# RB2_My.net
KiCad netlist of a schematic drawn in Altium Designer
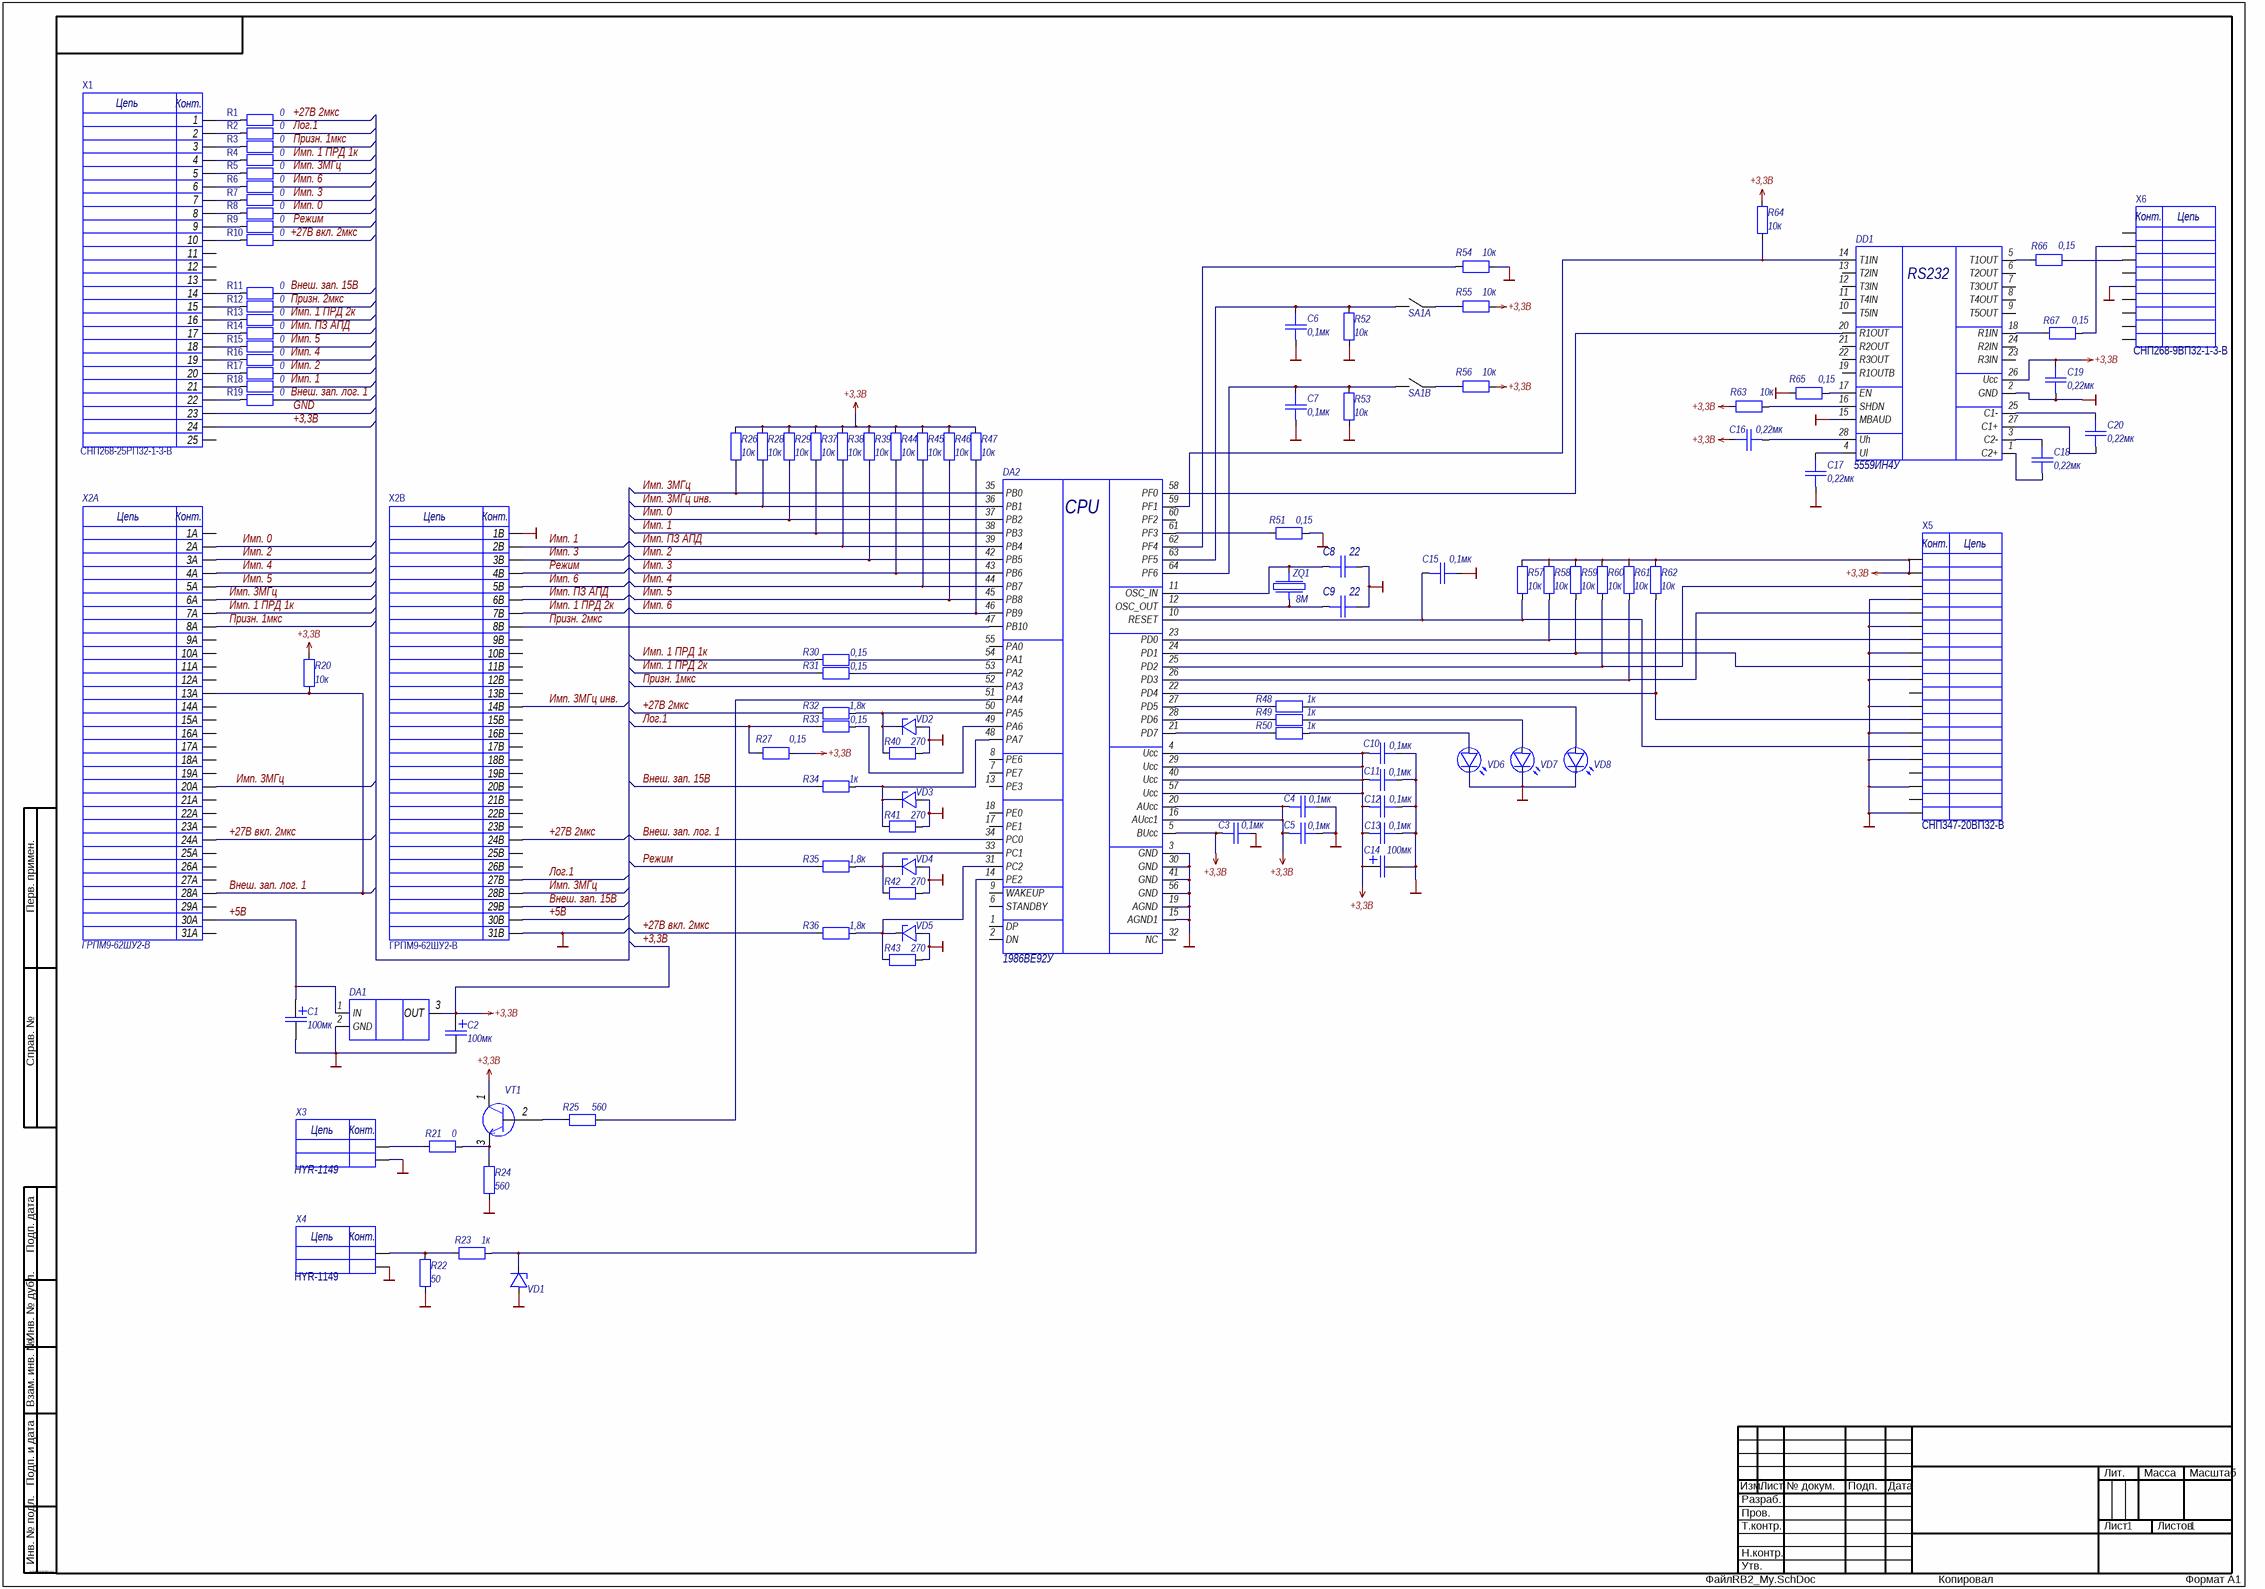
[diagram p0: RB2_My.SchDoc]

(export (version "E")
  (design (tool "Eeschema 10.0.6"))
  (components
    (comp (ref "C1")
      (value "100мк")
      (footprint "Chip2PinSM127P600-8N(E)")
      (description "Танталовый конденсатор")
      (fields (field (name "Comment") "К53-65-16В-100мкФАЖЯР.673546.004ТУ"))
      (libsource (lib "RB") (part "CapTan"))
    )
    (comp (ref "C2")
      (value "100мк")
      (footprint "Chip2PinSM127P600-8N(E)")
      (description "Танталовый конденсатор")
      (fields (field (name "Comment") "К53-65-16В-100мкФАЖЯР.673546.004ТУ"))
      (libsource (lib "RB") (part "CapTan"))
    )
    (comp (ref "C3")
      (value "0,1мк")
      (footprint "CAPC3419X15N(1206)")
      (description "Керамический конденсатор")
      (fields (field (name "Comment") "К10-17в-Н90-0,1мкФ-3ОЖО.460.107ТУ"))
      (libsource (lib "RB") (part "CapCer"))
    )
    (comp (ref "C4")
      (value "0,1мк")
      (footprint "CAPC3419X15N(1206)")
      (description "Керамический конденсатор")
      (fields (field (name "Comment") "К10-17в-Н90-0,1мкФ-3ОЖО.460.107ТУ"))
      (libsource (lib "RB") (part "CapCer"))
    )
    (comp (ref "C5")
      (value "0,1мк")
      (footprint "CAPC3419X15N(1206)")
      (description "Керамический конденсатор")
      (fields (field (name "Comment") "К10-17в-Н90-0,1мкФ-3ОЖО.460.107ТУ"))
      (libsource (lib "RB") (part "CapCer"))
    )
    (comp (ref "C6")
      (value "0,1мк")
      (footprint "CAPC3419X15N(1206)")
      (description "Керамический конденсатор")
      (fields (field (name "Comment") "К10-17в-Н90-0,1мкФ-3ОЖО.460.107ТУ"))
      (libsource (lib "RB") (part "CapCer"))
    )
    (comp (ref "C7")
      (value "0,1мк")
      (footprint "CAPC3419X15N(1206)")
      (description "Керамический конденсатор")
      (fields (field (name "Comment") "К10-17в-Н90-0,1мкФ-3ОЖО.460.107ТУ"))
      (libsource (lib "RB") (part "CapCer"))
    )
    (comp (ref "C8")
      (value "22")
      (footprint "CAPC1608X09N (0603)")
      (description "Керамический конденсатор")
      (fields (field (name "TOLERANCE") "10%") (field (name "Comment") "К10-17в-МПО-22Ф10%-1ОЖО.460.107ТУ"))
      (libsource (lib "RB") (part "CapCer_2"))
    )
    (comp (ref "C9")
      (value "22")
      (footprint "CAPC1608X09N (0603)")
      (description "Керамический конденсатор")
      (fields (field (name "TOLERANCE") "10%") (field (name "Comment") "К10-17в-МПО-22Ф10%-1ОЖО.460.107ТУ"))
      (libsource (lib "RB") (part "CapCer_2"))
    )
    (comp (ref "C10")
      (value "0,1мк")
      (footprint "CAPC3419X15N(1206)")
      (description "Керамический конденсатор")
      (fields (field (name "Comment") "К10-17в-Н90-0,1мкФ-3ОЖО.460.107ТУ"))
      (libsource (lib "RB") (part "CapCer"))
    )
    (comp (ref "C11")
      (value "0,1мк")
      (footprint "CAPC3419X15N(1206)")
      (description "Керамический конденсатор")
      (fields (field (name "Comment") "К10-17в-Н90-0,1мкФ-3ОЖО.460.107ТУ"))
      (libsource (lib "RB") (part "CapCer"))
    )
    (comp (ref "C12")
      (value "0,1мк")
      (footprint "CAPC3419X15N(1206)")
      (description "Керамический конденсатор")
      (fields (field (name "Comment") "К10-17в-Н90-0,1мкФ-3ОЖО.460.107ТУ"))
      (libsource (lib "RB") (part "CapCer"))
    )
    (comp (ref "C13")
      (value "0,1мк")
      (footprint "CAPC3419X15N(1206)")
      (description "Керамический конденсатор")
      (fields (field (name "Comment") "К10-17в-Н90-0,1мкФ-3ОЖО.460.107ТУ"))
      (libsource (lib "RB") (part "CapCer"))
    )
    (comp (ref "C14")
      (value "100мк")
      (footprint "Chip2PinSM127P600-8N(E)")
      (description "Танталовый конденсатор")
      (fields (field (name "Comment") "К53-65-16В-100мкФАЖЯР.673546.004ТУ"))
      (libsource (lib "RB") (part "CapTan"))
    )
    (comp (ref "C15")
      (value "0,1мк")
      (footprint "CAPC3419X15N(1206)")
      (description "Керамический конденсатор")
      (fields (field (name "Comment") "К10-17в-Н90-0,1мкФ-3ОЖО.460.107ТУ"))
      (libsource (lib "RB") (part "CapCer"))
    )
    (comp (ref "C16")
      (value "0,22мк")
      (footprint "CAPC3419X15N(1206)")
      (description "Керамический конденсатор")
      (fields (field (name "Comment") "К10-17в-Н30-0,22мкФ-3ОЖО.460.107ТУ"))
      (libsource (lib "RB") (part "CapCer_1"))
    )
    (comp (ref "C17")
      (value "0,22мк")
      (footprint "CAPC3419X15N(1206)")
      (description "Керамический конденсатор")
      (fields (field (name "Comment") "К10-17в-Н30-0,22мкФ-3ОЖО.460.107ТУ"))
      (libsource (lib "RB") (part "CapCer_1"))
    )
    (comp (ref "C18")
      (value "0,22мк")
      (footprint "CAPC3419X15N(1206)")
      (description "Керамический конденсатор")
      (fields (field (name "Comment") "К10-17в-Н30-0,22мкФ-3ОЖО.460.107ТУ"))
      (libsource (lib "RB") (part "CapCer_1"))
    )
    (comp (ref "C19")
      (value "0,22мк")
      (footprint "CAPC3419X15N(1206)")
      (description "Керамический конденсатор")
      (fields (field (name "Comment") "К10-17в-Н30-0,22мкФ-3ОЖО.460.107ТУ"))
      (libsource (lib "RB") (part "CapCer_1"))
    )
    (comp (ref "C20")
      (value "0,22мк")
      (footprint "CAPC3419X15N(1206)")
      (description "Керамический конденсатор")
      (fields (field (name "Comment") "К10-17в-Н30-0,22мкФ-3ОЖО.460.107ТУ"))
      (libsource (lib "RB") (part "CapCer_1"))
    )
    (comp (ref "DA1")
      (value "1303ЕН3.3ПАЕЯР.431420.638ТУ")
      (footprint "КТ-28А-2.01")
      (libsource (lib "RB") (part "Stabil"))
    )
    (comp (ref "DA2")
      (value "1986ВЕ92У")
      (footprint "1986ВЕ92У")
      (description "Микроконтроллер")
      (libsource (lib "RB") (part "1986ВЕ93"))
    )
    (comp (ref "DD1")
      (value "5559ИН4У")
      (footprint "5559ИН4У")
      (description "Приемопередатчик RS232")
      (libsource (lib "RB") (part "5559ИН4У"))
    )
    (comp (ref "R1")
      (value "0")
      (footprint "RESC1608X05N (0603)")
      (description "Резистор")
      (fields (field (name "TOLERANCE") "5%") (field (name "MANUFACTURER") "АЛЯР.434110.005ТУ"))
      (libsource (lib "RB") (part "Res_1"))
    )
    (comp (ref "R2")
      (value "0")
      (footprint "RESC1608X05N (0603)")
      (description "Резистор")
      (fields (field (name "TOLERANCE") "5%") (field (name "MANUFACTURER") "АЛЯР.434110.005ТУ"))
      (libsource (lib "RB") (part "Res_1"))
    )
    (comp (ref "R3")
      (value "0")
      (footprint "RESC1608X05N (0603)")
      (description "Резистор")
      (fields (field (name "TOLERANCE") "5%") (field (name "MANUFACTURER") "АЛЯР.434110.005ТУ"))
      (libsource (lib "RB") (part "Res_1"))
    )
    (comp (ref "R4")
      (value "0")
      (footprint "RESC1608X05N (0603)")
      (description "Резистор")
      (fields (field (name "TOLERANCE") "5%") (field (name "MANUFACTURER") "АЛЯР.434110.005ТУ"))
      (libsource (lib "RB") (part "Res_1"))
    )
    (comp (ref "R5")
      (value "0")
      (footprint "RESC1608X05N (0603)")
      (description "Резистор")
      (fields (field (name "TOLERANCE") "5%") (field (name "MANUFACTURER") "АЛЯР.434110.005ТУ"))
      (libsource (lib "RB") (part "Res_1"))
    )
    (comp (ref "R6")
      (value "0")
      (footprint "RESC1608X05N (0603)")
      (description "Резистор")
      (fields (field (name "TOLERANCE") "5%") (field (name "MANUFACTURER") "АЛЯР.434110.005ТУ"))
      (libsource (lib "RB") (part "Res_1"))
    )
    (comp (ref "R7")
      (value "0")
      (footprint "RESC1608X05N (0603)")
      (description "Резистор")
      (fields (field (name "TOLERANCE") "5%") (field (name "MANUFACTURER") "АЛЯР.434110.005ТУ"))
      (libsource (lib "RB") (part "Res_1"))
    )
    (comp (ref "R8")
      (value "0")
      (footprint "RESC1608X05N (0603)")
      (description "Резистор")
      (fields (field (name "TOLERANCE") "5%") (field (name "MANUFACTURER") "АЛЯР.434110.005ТУ"))
      (libsource (lib "RB") (part "Res_1"))
    )
    (comp (ref "R9")
      (value "0")
      (footprint "RESC1608X05N (0603)")
      (description "Резистор")
      (fields (field (name "TOLERANCE") "5%") (field (name "MANUFACTURER") "АЛЯР.434110.005ТУ"))
      (libsource (lib "RB") (part "Res_1"))
    )
    (comp (ref "R10")
      (value "0")
      (footprint "RESC1608X05N (0603)")
      (description "Резистор")
      (fields (field (name "TOLERANCE") "5%") (field (name "MANUFACTURER") "АЛЯР.434110.005ТУ"))
      (libsource (lib "RB") (part "Res_1"))
    )
    (comp (ref "R11")
      (value "0")
      (footprint "RESC1608X05N (0603)")
      (description "Резистор")
      (fields (field (name "TOLERANCE") "5%") (field (name "MANUFACTURER") "АЛЯР.434110.005ТУ"))
      (libsource (lib "RB") (part "Res_1"))
    )
    (comp (ref "R12")
      (value "0")
      (footprint "RESC1608X05N (0603)")
      (description "Резистор")
      (fields (field (name "TOLERANCE") "5%") (field (name "MANUFACTURER") "АЛЯР.434110.005ТУ"))
      (libsource (lib "RB") (part "Res_1"))
    )
    (comp (ref "R13")
      (value "0")
      (footprint "RESC1608X05N (0603)")
      (description "Резистор")
      (fields (field (name "TOLERANCE") "5%") (field (name "MANUFACTURER") "АЛЯР.434110.005ТУ"))
      (libsource (lib "RB") (part "Res_1"))
    )
    (comp (ref "R14")
      (value "0")
      (footprint "RESC1608X05N (0603)")
      (description "Резистор")
      (fields (field (name "TOLERANCE") "5%") (field (name "MANUFACTURER") "АЛЯР.434110.005ТУ"))
      (libsource (lib "RB") (part "Res_1"))
    )
    (comp (ref "R15")
      (value "0")
      (footprint "RESC1608X05N (0603)")
      (description "Резистор")
      (fields (field (name "TOLERANCE") "5%") (field (name "MANUFACTURER") "АЛЯР.434110.005ТУ"))
      (libsource (lib "RB") (part "Res_1"))
    )
    (comp (ref "R16")
      (value "0")
      (footprint "RESC1608X05N (0603)")
      (description "Резистор")
      (fields (field (name "TOLERANCE") "5%") (field (name "MANUFACTURER") "АЛЯР.434110.005ТУ"))
      (libsource (lib "RB") (part "Res_1"))
    )
    (comp (ref "R17")
      (value "0")
      (footprint "RESC1608X05N (0603)")
      (description "Резистор")
      (fields (field (name "TOLERANCE") "5%") (field (name "MANUFACTURER") "АЛЯР.434110.005ТУ"))
      (libsource (lib "RB") (part "Res_1"))
    )
    (comp (ref "R18")
      (value "0")
      (footprint "RESC1608X05N (0603)")
      (description "Резистор")
      (fields (field (name "TOLERANCE") "5%") (field (name "MANUFACTURER") "АЛЯР.434110.005ТУ"))
      (libsource (lib "RB") (part "Res_1"))
    )
    (comp (ref "R19")
      (value "0")
      (footprint "RESC1608X05N (0603)")
      (description "Резистор")
      (fields (field (name "TOLERANCE") "5%") (field (name "MANUFACTURER") "АЛЯР.434110.005ТУ"))
      (libsource (lib "RB") (part "Res_1"))
    )
    (comp (ref "R20")
      (value "10к")
      (footprint "RESC1608X05N (0603)")
      (description "Резистор")
      (fields (field (name "TOLERANCE") "5%") (field (name "MANUFACTURER") "АЛЯР.434110.005ТУ"))
      (libsource (lib "") (part "Res_7_1"))
    )
    (comp (ref "R21")
      (value "0")
      (footprint "RESC1608X05N (0603)")
      (description "Резистор")
      (fields (field (name "TOLERANCE") "5%") (field (name "MANUFACTURER") "АЛЯР.434110.005ТУ"))
      (libsource (lib "RB") (part "Res_1"))
    )
    (comp (ref "R22")
      (value "50")
      (footprint "RESC1608X05N (0603)")
      (description "Резистор")
      (fields (field (name "TOLERANCE") "5%") (field (name "MANUFACTURER") "АЛЯР.434110.005ТУ"))
      (libsource (lib "RB") (part "Res"))
    )
    (comp (ref "R23")
      (value "1к")
      (footprint "RESC1608X05N (0603)")
      (description "Резистор")
      (fields (field (name "TOLERANCE") "5%") (field (name "MANUFACTURER") "АЛЯР.434110.005ТУ"))
      (libsource (lib "RB") (part "Res_8"))
    )
    (comp (ref "R24")
      (value "560")
      (footprint "RESC1608X05N (0603)")
      (description "Резистор")
      (fields (field (name "TOLERANCE") "5%") (field (name "MANUFACTURER") "АЛЯР.434110.005ТУ"))
      (libsource (lib "RB") (part "Res_3"))
    )
    (comp (ref "R25")
      (value "560")
      (footprint "RESC1608X05N (0603)")
      (description "Резистор")
      (fields (field (name "TOLERANCE") "5%") (field (name "MANUFACTURER") "АЛЯР.434110.005ТУ"))
      (libsource (lib "") (part "Res_3_1"))
    )
    (comp (ref "R26")
      (value "10к")
      (footprint "RESC1608X05N (0603)")
      (description "Резистор")
      (fields (field (name "TOLERANCE") "5%") (field (name "MANUFACTURER") "АЛЯР.434110.005ТУ"))
      (libsource (lib "") (part "Res_7_1"))
    )
    (comp (ref "R27")
      (value "0,15")
      (footprint "RESC1608X05N (0603)")
      (description "Резистор")
      (fields (field (name "TOLERANCE") "5%") (field (name "MANUFACTURER") "АЛЯР.434110.005ТУ"))
      (libsource (lib "RB") (part "Res_4"))
    )
    (comp (ref "R28")
      (value "10к")
      (footprint "RESC1608X05N (0603)")
      (description "Резистор")
      (fields (field (name "TOLERANCE") "5%") (field (name "MANUFACTURER") "АЛЯР.434110.005ТУ"))
      (libsource (lib "") (part "Res_7_1"))
    )
    (comp (ref "R29")
      (value "10к")
      (footprint "RESC1608X05N (0603)")
      (description "Резистор")
      (fields (field (name "TOLERANCE") "5%") (field (name "MANUFACTURER") "АЛЯР.434110.005ТУ"))
      (libsource (lib "") (part "Res_7_1"))
    )
    (comp (ref "R30")
      (value "0,15")
      (footprint "RESC1608X05N (0603)")
      (description "Резистор")
      (fields (field (name "TOLERANCE") "5%") (field (name "MANUFACTURER") "АЛЯР.434110.005ТУ"))
      (libsource (lib "RB") (part "Res_4"))
    )
    (comp (ref "R31")
      (value "0,15")
      (footprint "RESC1608X05N (0603)")
      (description "Резистор")
      (fields (field (name "TOLERANCE") "5%") (field (name "MANUFACTURER") "АЛЯР.434110.005ТУ"))
      (libsource (lib "RB") (part "Res_4"))
    )
    (comp (ref "R32")
      (value "1,8к")
      (footprint "RESC1608X05N (0603)")
      (description "Резистор")
      (fields (field (name "TOLERANCE") "5%") (field (name "MANUFACTURER") "АЛЯР.434110.005ТУ"))
      (libsource (lib "RB") (part "Res_5"))
    )
    (comp (ref "R33")
      (value "0,15")
      (footprint "RESC1608X05N (0603)")
      (description "Резистор")
      (fields (field (name "TOLERANCE") "5%") (field (name "MANUFACTURER") "АЛЯР.434110.005ТУ"))
      (libsource (lib "RB") (part "Res_4"))
    )
    (comp (ref "R34")
      (value "1к")
      (footprint "RESC1608X05N (0603)")
      (description "Резистор")
      (fields (field (name "TOLERANCE") "5%") (field (name "MANUFACTURER") "АЛЯР.434110.005ТУ"))
      (libsource (lib "RB") (part "Res_8"))
    )
    (comp (ref "R35")
      (value "1,8к")
      (footprint "RESC1608X05N (0603)")
      (description "Резистор")
      (fields (field (name "TOLERANCE") "5%") (field (name "MANUFACTURER") "АЛЯР.434110.005ТУ"))
      (libsource (lib "RB") (part "Res_5"))
    )
    (comp (ref "R36")
      (value "1,8к")
      (footprint "RESC1608X05N (0603)")
      (description "Резистор")
      (fields (field (name "TOLERANCE") "5%") (field (name "MANUFACTURER") "АЛЯР.434110.005ТУ"))
      (libsource (lib "RB") (part "Res_5"))
    )
    (comp (ref "R37")
      (value "10к")
      (footprint "RESC1608X05N (0603)")
      (description "Резистор")
      (fields (field (name "TOLERANCE") "5%") (field (name "MANUFACTURER") "АЛЯР.434110.005ТУ"))
      (libsource (lib "") (part "Res_7_1"))
    )
    (comp (ref "R38")
      (value "10к")
      (footprint "RESC1608X05N (0603)")
      (description "Резистор")
      (fields (field (name "TOLERANCE") "5%") (field (name "MANUFACTURER") "АЛЯР.434110.005ТУ"))
      (libsource (lib "") (part "Res_7_1"))
    )
    (comp (ref "R39")
      (value "10к")
      (footprint "RESC1608X05N (0603)")
      (description "Резистор")
      (fields (field (name "TOLERANCE") "5%") (field (name "MANUFACTURER") "АЛЯР.434110.005ТУ"))
      (libsource (lib "") (part "Res_7_1"))
    )
    (comp (ref "R40")
      (value "270")
      (footprint "RESC1608X05N (0603)")
      (description "Резистор")
      (fields (field (name "TOLERANCE") "5%") (field (name "MANUFACTURER") "АЛЯР.434110.005ТУ"))
      (libsource (lib "RB") (part "Res_6"))
    )
    (comp (ref "R41")
      (value "270")
      (footprint "RESC1608X05N (0603)")
      (description "Резистор")
      (fields (field (name "TOLERANCE") "5%") (field (name "MANUFACTURER") "АЛЯР.434110.005ТУ"))
      (libsource (lib "RB") (part "Res_6"))
    )
    (comp (ref "R42")
      (value "270")
      (footprint "RESC1608X05N (0603)")
      (description "Резистор")
      (fields (field (name "TOLERANCE") "5%") (field (name "MANUFACTURER") "АЛЯР.434110.005ТУ"))
      (libsource (lib "RB") (part "Res_6"))
    )
    (comp (ref "R43")
      (value "270")
      (footprint "RESC1608X05N (0603)")
      (description "Резистор")
      (fields (field (name "TOLERANCE") "5%") (field (name "MANUFACTURER") "АЛЯР.434110.005ТУ"))
      (libsource (lib "RB") (part "Res_6"))
    )
    (comp (ref "R44")
      (value "10к")
      (footprint "RESC1608X05N (0603)")
      (description "Резистор")
      (fields (field (name "TOLERANCE") "5%") (field (name "MANUFACTURER") "АЛЯР.434110.005ТУ"))
      (libsource (lib "") (part "Res_7_1"))
    )
    (comp (ref "R45")
      (value "10к")
      (footprint "RESC1608X05N (0603)")
      (description "Резистор")
      (fields (field (name "TOLERANCE") "5%") (field (name "MANUFACTURER") "АЛЯР.434110.005ТУ"))
      (libsource (lib "") (part "Res_7_1"))
    )
    (comp (ref "R46")
      (value "10к")
      (footprint "RESC1608X05N (0603)")
      (description "Резистор")
      (fields (field (name "TOLERANCE") "5%") (field (name "MANUFACTURER") "АЛЯР.434110.005ТУ"))
      (libsource (lib "") (part "Res_7_1"))
    )
    (comp (ref "R47")
      (value "10к")
      (footprint "RESC1608X05N (0603)")
      (description "Резистор")
      (fields (field (name "TOLERANCE") "5%") (field (name "MANUFACTURER") "АЛЯР.434110.005ТУ"))
      (libsource (lib "") (part "Res_7_1"))
    )
    (comp (ref "R48")
      (value "1к")
      (footprint "RESC1608X05N (0603)")
      (description "Резистор")
      (fields (field (name "TOLERANCE") "5%") (field (name "MANUFACTURER") "АЛЯР.434110.005ТУ"))
      (libsource (lib "RB") (part "Res_8"))
    )
    (comp (ref "R49")
      (value "1к")
      (footprint "RESC1608X05N (0603)")
      (description "Резистор")
      (fields (field (name "TOLERANCE") "5%") (field (name "MANUFACTURER") "АЛЯР.434110.005ТУ"))
      (libsource (lib "RB") (part "Res_8"))
    )
    (comp (ref "R50")
      (value "1к")
      (footprint "RESC1608X05N (0603)")
      (description "Резистор")
      (fields (field (name "TOLERANCE") "5%") (field (name "MANUFACTURER") "АЛЯР.434110.005ТУ"))
      (libsource (lib "RB") (part "Res_8"))
    )
    (comp (ref "R51")
      (value "0,15")
      (footprint "RESC1608X05N (0603)")
      (description "Резистор")
      (fields (field (name "TOLERANCE") "5%") (field (name "MANUFACTURER") "АЛЯР.434110.005ТУ"))
      (libsource (lib "") (part "Res_4_1"))
    )
    (comp (ref "R52")
      (value "10к")
      (footprint "RESC1608X05N (0603)")
      (description "Резистор")
      (fields (field (name "TOLERANCE") "5%") (field (name "MANUFACTURER") "АЛЯР.434110.005ТУ"))
      (libsource (lib "") (part "Res_7_1"))
    )
    (comp (ref "R53")
      (value "10к")
      (footprint "RESC1608X05N (0603)")
      (description "Резистор")
      (fields (field (name "TOLERANCE") "5%") (field (name "MANUFACTURER") "АЛЯР.434110.005ТУ"))
      (libsource (lib "") (part "Res_7_1"))
    )
    (comp (ref "R54")
      (value "10к")
      (footprint "RESC1608X05N (0603)")
      (description "Резистор")
      (fields (field (name "TOLERANCE") "5%") (field (name "MANUFACTURER") "АЛЯР.434110.005ТУ"))
      (libsource (lib "") (part "Res_7_2"))
    )
    (comp (ref "R55")
      (value "10к")
      (footprint "RESC1608X05N (0603)")
      (description "Резистор")
      (fields (field (name "TOLERANCE") "5%") (field (name "MANUFACTURER") "АЛЯР.434110.005ТУ"))
      (libsource (lib "") (part "Res_7_2"))
    )
    (comp (ref "R56")
      (value "10к")
      (footprint "RESC1608X05N (0603)")
      (description "Резистор")
      (fields (field (name "TOLERANCE") "5%") (field (name "MANUFACTURER") "АЛЯР.434110.005ТУ"))
      (libsource (lib "") (part "Res_7_2"))
    )
    (comp (ref "R57")
      (value "10к")
      (footprint "RESC1608X05N (0603)")
      (description "Резистор")
      (fields (field (name "TOLERANCE") "5%") (field (name "MANUFACTURER") "АЛЯР.434110.005ТУ"))
      (libsource (lib "RB") (part "Res_7"))
    )
    (comp (ref "R58")
      (value "10к")
      (footprint "RESC1608X05N (0603)")
      (description "Резистор")
      (fields (field (name "TOLERANCE") "5%") (field (name "MANUFACTURER") "АЛЯР.434110.005ТУ"))
      (libsource (lib "RB") (part "Res_7"))
    )
    (comp (ref "R59")
      (value "10к")
      (footprint "RESC1608X05N (0603)")
      (description "Резистор")
      (fields (field (name "TOLERANCE") "5%") (field (name "MANUFACTURER") "АЛЯР.434110.005ТУ"))
      (libsource (lib "RB") (part "Res_7"))
    )
    (comp (ref "R60")
      (value "10к")
      (footprint "RESC1608X05N (0603)")
      (description "Резистор")
      (fields (field (name "TOLERANCE") "5%") (field (name "MANUFACTURER") "АЛЯР.434110.005ТУ"))
      (libsource (lib "RB") (part "Res_7"))
    )
    (comp (ref "R61")
      (value "10к")
      (footprint "RESC1608X05N (0603)")
      (description "Резистор")
      (fields (field (name "TOLERANCE") "5%") (field (name "MANUFACTURER") "АЛЯР.434110.005ТУ"))
      (libsource (lib "RB") (part "Res_7"))
    )
    (comp (ref "R62")
      (value "10к")
      (footprint "RESC1608X05N (0603)")
      (description "Резистор")
      (fields (field (name "TOLERANCE") "5%") (field (name "MANUFACTURER") "АЛЯР.434110.005ТУ"))
      (libsource (lib "RB") (part "Res_7"))
    )
    (comp (ref "R63")
      (value "10к")
      (footprint "RESC1608X05N (0603)")
      (description "Резистор")
      (fields (field (name "TOLERANCE") "5%") (field (name "MANUFACTURER") "АЛЯР.434110.005ТУ"))
      (libsource (lib "") (part "Res_7_2"))
    )
    (comp (ref "R64")
      (value "10к")
      (footprint "RESC1608X05N (0603)")
      (description "Резистор")
      (fields (field (name "TOLERANCE") "5%") (field (name "MANUFACTURER") "АЛЯР.434110.005ТУ"))
      (libsource (lib "") (part "Res_7_1"))
    )
    (comp (ref "R65")
      (value "0,15")
      (footprint "RESC1608X05N (0603)")
      (description "Резистор")
      (fields (field (name "TOLERANCE") "5%") (field (name "MANUFACTURER") "АЛЯР.434110.005ТУ"))
      (libsource (lib "RB") (part "Res_4"))
    )
    (comp (ref "R66")
      (value "0,15")
      (footprint "RESC1608X05N (0603)")
      (description "Резистор")
      (fields (field (name "TOLERANCE") "5%") (field (name "MANUFACTURER") "АЛЯР.434110.005ТУ"))
      (libsource (lib "RB") (part "Res_4"))
    )
    (comp (ref "R67")
      (value "0,15")
      (footprint "RESC1608X05N (0603)")
      (description "Резистор")
      (fields (field (name "TOLERANCE") "5%") (field (name "MANUFACTURER") "АЛЯР.434110.005ТУ"))
      (libsource (lib "RB") (part "Res_4"))
    )
    (comp (ref "SA1")
      (value "DS1040-02RN")
      (footprint "DS1040-02RN")
      (description "Переключатель")
      (libsource (lib "RB") (part "Switch"))
    )
    (comp (ref "VD1")
      (value "2С133аА0.339.092ТУ")
      (footprint "2С127Д-1")
      (libsource (lib "RB") (part "2С127Д-1"))
    )
    (comp (ref "VD2")
      (value "2С133аА0.339.092ТУ")
      (footprint "2С127Д-1")
      (libsource (lib "RB") (part "2С127Д-1"))
    )
    (comp (ref "VD3")
      (value "2С133аА0.339.092ТУ")
      (footprint "2С127Д-1")
      (libsource (lib "RB") (part "2С127Д-1"))
    )
    (comp (ref "VD4")
      (value "2С133аА0.339.092ТУ")
      (footprint "2С127Д-1")
      (libsource (lib "RB") (part "2С127Д-1"))
    )
    (comp (ref "VD5")
      (value "2С133аА0.339.092ТУ")
      (footprint "2С127Д-1")
      (libsource (lib "RB") (part "2С127Д-1"))
    )
    (comp (ref "VD6")
      (value "3Л341БаА0.339.189ТУ")
      (footprint "3Л341Б")
      (description "Индикатор")
      (libsource (lib "RB") (part "Led"))
    )
    (comp (ref "VD7")
      (value "3Л341БаА0.339.189ТУ")
      (footprint "3Л341Б")
      (description "Индикатор")
      (libsource (lib "RB") (part "Led"))
    )
    (comp (ref "VD8")
      (value "3Л341БаА0.339.189ТУ")
      (footprint "3Л341Б")
      (description "Индикатор")
      (libsource (lib "RB") (part "Led"))
    )
    (comp (ref "VT1")
      (value "2Т368А9аА0.339.092ТУ")
      (footprint "SOT100P230X95-3N (2T368A9)")
      (description "NPN транзистор")
      (libsource (lib "RB") (part "2Т368А"))
    )
    (comp (ref "X1")
      (value "СНП268-25РП32-1-3-В")
      (footprint "СНП268-25РП32-1-4-В")
      (libsource (lib "RB") (part "СНП268-25РП"))
    )
    (comp (ref "X2")
      (value "ГРПМ9-62ШУ2-В")
      (footprint "ГРПМ9-62ШУ2-В")
      (libsource (lib "RB") (part "GRPM9-62"))
    )
    (comp (ref "X3") (value "HYR-1149") (footprint "HYR-1149") (libsource (lib "RB") (part "SMA")))
    (comp (ref "X4") (value "HYR-1149") (footprint "HYR-1149") (libsource (lib "RB") (part "SMA")))
    (comp (ref "X5")
      (value "СНП347-20ВП32-В")
      (footprint "СНП347-20ВП22-В")
      (libsource (lib "RB") (part "СНП347-20ВП"))
    )
    (comp (ref "X6")
      (value "СНП268-9ВП32-1-3-В")
      (footprint "СНП268-9ВП32-1-4-В")
      (libsource (lib "RB") (part "СНП268-9ВП"))
    )
    (comp (ref "ZQ1")
      (value "8М")
      (footprint "РК456")
      (description "Кварцевый резонатор")
      (fields (field (name "Comment") "РК386-П-8ДТ-8000КТУ6321-004-07614320-96"))
      (libsource (lib "RB") (part "XTAL"))
    )
  )
  (nets
    (net (code "1") (name "+3,3В") (class "Default")
      (node (ref "C10") (pin "1") (pinfunction "1_1") (pintype "passive"))
      (node (ref "C11") (pin "1") (pinfunction "1_1") (pintype "passive"))
      (node (ref "C12") (pin "1") (pinfunction "1_1") (pintype "passive"))
      (node (ref "C13") (pin "1") (pinfunction "1_1") (pintype "passive"))
      (node (ref "C14") (pin "1") (pinfunction "1_1") (pintype "passive"))
      (node (ref "C16") (pin "2") (pinfunction "2_2") (pintype "passive"))
      (node (ref "C19") (pin "2") (pinfunction "2_2") (pintype "passive"))
      (node (ref "C2") (pin "1") (pinfunction "1_1") (pintype "passive"))
      (node (ref "C3") (pin "1") (pinfunction "1_1") (pintype "passive"))
      (node (ref "C4") (pin "1") (pinfunction "1_1") (pintype "passive"))
      (node (ref "C5") (pin "1") (pinfunction "1_1") (pintype "passive"))
      (node (ref "DA1") (pin "3") (pinfunction "OUT_3") (pintype "passive"))
      (node (ref "DA2") (pin "16") (pinfunction "AUcc1_16") (pintype "passive"))
      (node (ref "DA2") (pin "20") (pinfunction "AUcc_20") (pintype "passive"))
      (node (ref "DA2") (pin "29") (pinfunction "Ucc_29") (pintype "passive"))
      (node (ref "DA2") (pin "4") (pinfunction "Ucc_4") (pintype "passive"))
      (node (ref "DA2") (pin "40") (pinfunction "Ucc_40") (pintype "passive"))
      (node (ref "DA2") (pin "5") (pinfunction "BUcc_5") (pintype "passive"))
      (node (ref "DA2") (pin "57") (pinfunction "Ucc_57") (pintype "passive"))
      (node (ref "DD1") (pin "26") (pinfunction "Ucc_26") (pintype "passive"))
      (node (ref "R20") (pin "2") (pinfunction "2_2") (pintype "passive"))
      (node (ref "R26") (pin "2") (pinfunction "2_2") (pintype "passive"))
      (node (ref "R27") (pin "2") (pinfunction "2_2") (pintype "passive"))
      (node (ref "R28") (pin "2") (pinfunction "2_2") (pintype "passive"))
      (node (ref "R29") (pin "2") (pinfunction "2_2") (pintype "passive"))
      (node (ref "R37") (pin "2") (pinfunction "2_2") (pintype "passive"))
      (node (ref "R38") (pin "2") (pinfunction "2_2") (pintype "passive"))
      (node (ref "R39") (pin "2") (pinfunction "2_2") (pintype "passive"))
      (node (ref "R44") (pin "2") (pinfunction "2_2") (pintype "passive"))
      (node (ref "R45") (pin "2") (pinfunction "2_2") (pintype "passive"))
      (node (ref "R46") (pin "2") (pinfunction "2_2") (pintype "passive"))
      (node (ref "R47") (pin "2") (pinfunction "2_2") (pintype "passive"))
      (node (ref "R55") (pin "2") (pinfunction "2_2") (pintype "passive"))
      (node (ref "R56") (pin "2") (pinfunction "2_2") (pintype "passive"))
      (node (ref "R57") (pin "1") (pinfunction "1_1") (pintype "passive"))
      (node (ref "R58") (pin "1") (pinfunction "1_1") (pintype "passive"))
      (node (ref "R59") (pin "1") (pinfunction "1_1") (pintype "passive"))
      (node (ref "R60") (pin "1") (pinfunction "1_1") (pintype "passive"))
      (node (ref "R61") (pin "1") (pinfunction "1_1") (pintype "passive"))
      (node (ref "R62") (pin "1") (pinfunction "1_1") (pintype "passive"))
      (node (ref "R63") (pin "1") (pinfunction "1_1") (pintype "passive"))
      (node (ref "R64") (pin "2") (pinfunction "2_2") (pintype "passive"))
      (node (ref "VT1") (pin "1") (pinfunction "1_1") (pintype "passive"))
      (node (ref "X1") (pin "24") (pinfunction "24_24") (pintype "passive"))
      (node (ref "X5") (pin "1") (pintype "passive"))
      (node (ref "X5") (pin "2") (pintype "passive"))
    )
    (net (code "2") (name "/+5В") (class "Default")
      (node (ref "C1") (pin "1") (pinfunction "1_1") (pintype "passive"))
      (node (ref "DA1") (pin "1") (pinfunction "IN_1") (pintype "passive"))
      (node (ref "X2") (pin "30A") (pinfunction "30A_30A") (pintype "passive"))
      (node (ref "X2") (pin "30B") (pinfunction "30B_30B") (pintype "passive"))
    )
    (net (code "3") (name "/+27В 2мкс") (class "Default")
      (node (ref "R1") (pin "2") (pinfunction "2_2") (pintype "passive"))
      (node (ref "R32") (pin "1") (pinfunction "1_1") (pintype "passive"))
      (node (ref "X2") (pin "24B") (pinfunction "24B_24B") (pintype "passive"))
    )
    (net (code "4") (name "/+27В вкл. 2мкс") (class "Default")
      (node (ref "R10") (pin "2") (pinfunction "2_2") (pintype "passive"))
      (node (ref "R36") (pin "1") (pinfunction "1_1") (pintype "passive"))
      (node (ref "X2") (pin "24A") (pinfunction "24A_24A") (pintype "passive"))
    )
    (net (code "5") (name "/Внеш. зап. 15В") (class "Default")
      (node (ref "R11") (pin "2") (pinfunction "2_2") (pintype "passive"))
      (node (ref "R34") (pin "1") (pinfunction "1_1") (pintype "passive"))
      (node (ref "X2") (pin "29B") (pinfunction "29B_29B") (pintype "passive"))
    )
    (net (code "6") (name "/Внеш. зап. лог. 1") (class "Default")
      (node (ref "DA2") (pin "34") (pinfunction "PC0_34") (pintype "passive"))
      (node (ref "R19") (pin "2") (pinfunction "2_2") (pintype "passive"))
      (node (ref "R20") (pin "1") (pinfunction "1_1") (pintype "passive"))
      (node (ref "X2") (pin "13A") (pinfunction "13A_13A") (pintype "passive"))
      (node (ref "X2") (pin "28A") (pinfunction "28A_28A") (pintype "passive"))
    )
    (net (code "7") (name "/Имп. 0") (class "Default")
      (node (ref "DA2") (pin "37") (pinfunction "PB2_37") (pintype "passive"))
      (node (ref "R29") (pin "1") (pinfunction "1_1") (pintype "passive"))
      (node (ref "R8") (pin "2") (pinfunction "2_2") (pintype "passive"))
      (node (ref "X2") (pin "2A") (pinfunction "2A_2A") (pintype "passive"))
    )
    (net (code "8") (name "/Имп. 1") (class "Default")
      (node (ref "DA2") (pin "38") (pinfunction "PB3_38") (pintype "passive"))
      (node (ref "R18") (pin "2") (pinfunction "2_2") (pintype "passive"))
      (node (ref "R37") (pin "1") (pinfunction "1_1") (pintype "passive"))
      (node (ref "X2") (pin "2B") (pinfunction "2B_2B") (pintype "passive"))
    )
    (net (code "9") (name "/Имп. 1 ПРД 1к") (class "Default")
      (node (ref "R30") (pin "1") (pinfunction "1_1") (pintype "passive"))
      (node (ref "R4") (pin "2") (pinfunction "2_2") (pintype "passive"))
      (node (ref "X2") (pin "7A") (pinfunction "7A_7A") (pintype "passive"))
    )
    (net (code "10") (name "/Имп. 1 ПРД 2к") (class "Default")
      (node (ref "R13") (pin "2") (pinfunction "2_2") (pintype "passive"))
      (node (ref "R31") (pin "1") (pinfunction "1_1") (pintype "passive"))
      (node (ref "X2") (pin "7B") (pinfunction "7B_7B") (pintype "passive"))
    )
    (net (code "11") (name "/Имп. 2") (class "Default")
      (node (ref "DA2") (pin "42") (pinfunction "PB5_42") (pintype "passive"))
      (node (ref "R17") (pin "2") (pinfunction "2_2") (pintype "passive"))
      (node (ref "R39") (pin "1") (pinfunction "1_1") (pintype "passive"))
      (node (ref "X2") (pin "3A") (pinfunction "3A_3A") (pintype "passive"))
    )
    (net (code "12") (name "/Имп. 3") (class "Default")
      (node (ref "DA2") (pin "43") (pinfunction "PB6_43") (pintype "passive"))
      (node (ref "R44") (pin "1") (pinfunction "1_1") (pintype "passive"))
      (node (ref "R7") (pin "2") (pinfunction "2_2") (pintype "passive"))
      (node (ref "X2") (pin "3B") (pinfunction "3B_3B") (pintype "passive"))
    )
    (net (code "13") (name "/Имп. 3МГц") (class "Default")
      (node (ref "DA2") (pin "35") (pinfunction "PB0_35") (pintype "passive"))
      (node (ref "R26") (pin "1") (pinfunction "1_1") (pintype "passive"))
      (node (ref "R5") (pin "2") (pinfunction "2_2") (pintype "passive"))
      (node (ref "X2") (pin "20A") (pinfunction "20A_20A") (pintype "passive"))
      (node (ref "X2") (pin "28B") (pinfunction "28B_28B") (pintype "passive"))
      (node (ref "X2") (pin "6A") (pinfunction "6A_6A") (pintype "passive"))
    )
    (net (code "14") (name "/Имп. 3МГц инв.") (class "Default")
      (node (ref "DA2") (pin "36") (pinfunction "PB1_36") (pintype "passive"))
      (node (ref "R28") (pin "1") (pinfunction "1_1") (pintype "passive"))
      (node (ref "X2") (pin "14B") (pinfunction "14B_14B") (pintype "passive"))
    )
    (net (code "15") (name "/Имп. 4") (class "Default")
      (node (ref "DA2") (pin "44") (pinfunction "PB7_44") (pintype "passive"))
      (node (ref "R16") (pin "2") (pinfunction "2_2") (pintype "passive"))
      (node (ref "R45") (pin "1") (pinfunction "1_1") (pintype "passive"))
      (node (ref "X2") (pin "4A") (pinfunction "4A_4A") (pintype "passive"))
    )
    (net (code "16") (name "/Имп. 5") (class "Default")
      (node (ref "DA2") (pin "45") (pinfunction "PB8_45") (pintype "passive"))
      (node (ref "R15") (pin "2") (pinfunction "2_2") (pintype "passive"))
      (node (ref "R46") (pin "1") (pinfunction "1_1") (pintype "passive"))
      (node (ref "X2") (pin "5A") (pinfunction "5A_5A") (pintype "passive"))
    )
    (net (code "17") (name "/Имп. 6") (class "Default")
      (node (ref "DA2") (pin "46") (pinfunction "PB9_46") (pintype "passive"))
      (node (ref "R47") (pin "1") (pinfunction "1_1") (pintype "passive"))
      (node (ref "R6") (pin "2") (pinfunction "2_2") (pintype "passive"))
      (node (ref "X2") (pin "5B") (pinfunction "5B_5B") (pintype "passive"))
    )
    (net (code "18") (name "/Имп. ПЗ АПД") (class "Default")
      (node (ref "DA2") (pin "39") (pinfunction "PB4_39") (pintype "passive"))
      (node (ref "R14") (pin "2") (pinfunction "2_2") (pintype "passive"))
      (node (ref "R38") (pin "1") (pinfunction "1_1") (pintype "passive"))
      (node (ref "X2") (pin "6B") (pinfunction "6B_6B") (pintype "passive"))
    )
    (net (code "19") (name "/Лог.1") (class "Default")
      (node (ref "R2") (pin "2") (pinfunction "2_2") (pintype "passive"))
      (node (ref "R27") (pin "1") (pinfunction "1_1") (pintype "passive"))
      (node (ref "R33") (pin "1") (pinfunction "1_1") (pintype "passive"))
      (node (ref "X2") (pin "27B") (pinfunction "27B_27B") (pintype "passive"))
    )
    (net (code "20") (name "/Призн. 1мкс") (class "Default")
      (node (ref "DA2") (pin "52") (pinfunction "PA3_52") (pintype "passive"))
      (node (ref "R3") (pin "2") (pinfunction "2_2") (pintype "passive"))
      (node (ref "X2") (pin "8A") (pinfunction "8A_8A") (pintype "passive"))
    )
    (net (code "21") (name "/Призн. 2мкс") (class "Default")
      (node (ref "DA2") (pin "47") (pinfunction "PB10_47") (pintype "passive"))
      (node (ref "R12") (pin "2") (pinfunction "2_2") (pintype "passive"))
      (node (ref "X2") (pin "8B") (pinfunction "8B_8B") (pintype "passive"))
    )
    (net (code "22") (name "/Режим") (class "Default")
      (node (ref "R35") (pin "1") (pinfunction "1_1") (pintype "passive"))
      (node (ref "R9") (pin "2") (pinfunction "2_2") (pintype "passive"))
      (node (ref "X2") (pin "4B") (pinfunction "4B_4B") (pintype "passive"))
    )
    (net (code "23") (name "GND") (class "Default")
      (node (ref "C1") (pin "2") (pinfunction "2_2") (pintype "passive"))
      (node (ref "C10") (pin "2") (pinfunction "2_2") (pintype "passive"))
      (node (ref "C11") (pin "2") (pinfunction "2_2") (pintype "passive"))
      (node (ref "C12") (pin "2") (pinfunction "2_2") (pintype "passive"))
      (node (ref "C13") (pin "2") (pinfunction "2_2") (pintype "passive"))
      (node (ref "C14") (pin "2") (pinfunction "2_2") (pintype "passive"))
      (node (ref "C15") (pin "2") (pinfunction "2_2") (pintype "passive"))
      (node (ref "C17") (pin "1") (pinfunction "1_1") (pintype "passive"))
      (node (ref "C19") (pin "1") (pinfunction "1_1") (pintype "passive"))
      (node (ref "C2") (pin "2") (pinfunction "2_2") (pintype "passive"))
      (node (ref "C3") (pin "2") (pinfunction "2_2") (pintype "passive"))
      (node (ref "C4") (pin "2") (pinfunction "2_2") (pintype "passive"))
      (node (ref "C5") (pin "2") (pinfunction "2_2") (pintype "passive"))
      (node (ref "C6") (pin "1") (pinfunction "1_1") (pintype "passive"))
      (node (ref "C7") (pin "1") (pinfunction "1_1") (pintype "passive"))
      (node (ref "C8") (pin "2") (pinfunction "2_2") (pintype "passive"))
      (node (ref "C9") (pin "2") (pinfunction "2_2") (pintype "passive"))
      (node (ref "DA1") (pin "2") (pinfunction "GND_2") (pintype "passive"))
      (node (ref "DA2") (pin "15") (pinfunction "AGND1_15") (pintype "passive"))
      (node (ref "DA2") (pin "19") (pinfunction "AGND_19") (pintype "passive"))
      (node (ref "DA2") (pin "3") (pinfunction "GND_3") (pintype "passive"))
      (node (ref "DA2") (pin "30") (pinfunction "GND_30") (pintype "passive"))
      (node (ref "DA2") (pin "41") (pinfunction "GND_41") (pintype "passive"))
      (node (ref "DA2") (pin "56") (pinfunction "GND_56") (pintype "passive"))
      (node (ref "DD1") (pin "15") (pinfunction "MBAUD_15") (pintype "passive"))
      (node (ref "DD1") (pin "2") (pinfunction "GND_2") (pintype "passive"))
      (node (ref "R22") (pin "1") (pinfunction "1_1") (pintype "passive"))
      (node (ref "R24") (pin "1") (pinfunction "1_1") (pintype "passive"))
      (node (ref "R40") (pin "2") (pinfunction "2_2") (pintype "passive"))
      (node (ref "R41") (pin "2") (pinfunction "2_2") (pintype "passive"))
      (node (ref "R42") (pin "2") (pinfunction "2_2") (pintype "passive"))
      (node (ref "R43") (pin "2") (pinfunction "2_2") (pintype "passive"))
      (node (ref "R51") (pin "1") (pinfunction "1_1") (pintype "passive"))
      (node (ref "R52") (pin "1") (pinfunction "1_1") (pintype "passive"))
      (node (ref "R53") (pin "1") (pinfunction "1_1") (pintype "passive"))
      (node (ref "R54") (pin "2") (pinfunction "2_2") (pintype "passive"))
      (node (ref "R65") (pin "1") (pinfunction "1_1") (pintype "passive"))
      (node (ref "VD1") (pin "1") (pinfunction "1_1") (pintype "passive"))
      (node (ref "VD2") (pin "1") (pinfunction "1_1") (pintype "passive"))
      (node (ref "VD3") (pin "1") (pinfunction "1_1") (pintype "passive"))
      (node (ref "VD4") (pin "1") (pinfunction "1_1") (pintype "passive"))
      (node (ref "VD5") (pin "1") (pinfunction "1_1") (pintype "passive"))
      (node (ref "VD6") (pin "2") (pinfunction "2_2") (pintype "passive"))
      (node (ref "VD7") (pin "2") (pinfunction "2_2") (pintype "passive"))
      (node (ref "VD8") (pin "2") (pinfunction "2_2") (pintype "passive"))
      (node (ref "X1") (pin "23") (pinfunction "23_23") (pintype "passive"))
      (node (ref "X2") (pin "1B") (pinfunction "1B_1B") (pintype "passive"))
      (node (ref "X2") (pin "31B") (pinfunction "31B_31B") (pintype "passive"))
      (node (ref "X3") (pin "2") (pintype "passive"))
      (node (ref "X4") (pin "2") (pintype "passive"))
      (node (ref "X5") (pin "10") (pintype "passive"))
      (node (ref "X5") (pin "12") (pintype "passive"))
      (node (ref "X5") (pin "14") (pintype "passive"))
      (node (ref "X5") (pin "16") (pintype "passive"))
      (node (ref "X5") (pin "18") (pintype "passive"))
      (node (ref "X5") (pin "20") (pintype "passive"))
      (node (ref "X5") (pin "4") (pintype "passive"))
      (node (ref "X5") (pin "6") (pintype "passive"))
      (node (ref "X5") (pin "8") (pintype "passive"))
      (node (ref "X6") (pin "5") (pintype "power_in"))
    )
    (net (code "24") (name "Net-(DA2-OSC_IN)") (class "Default")
      (node (ref "C8") (pin "1") (pinfunction "1_1") (pintype "passive"))
      (node (ref "DA2") (pin "11") (pinfunction "OSC_IN_11") (pintype "passive"))
      (node (ref "ZQ1") (pin "2") (pinfunction "OSC2_2") (pintype "passive"))
    )
    (net (code "25") (name "Net-(DA2-OSC_OUT)") (class "Default")
      (node (ref "C9") (pin "1") (pinfunction "1_1") (pintype "passive"))
      (node (ref "DA2") (pin "12") (pinfunction "OSC_OUT_12") (pintype "passive"))
      (node (ref "ZQ1") (pin "1") (pinfunction "OSC1_1") (pintype "passive"))
    )
    (net (code "26") (name "Net-(DA2-PA1)") (class "Default")
      (node (ref "DA2") (pin "54") (pinfunction "PA1_54") (pintype "passive"))
      (node (ref "R30") (pin "2") (pinfunction "2_2") (pintype "passive"))
    )
    (net (code "27") (name "Net-(DA2-PA2)") (class "Default")
      (node (ref "DA2") (pin "53") (pinfunction "PA2_53") (pintype "passive"))
      (node (ref "R31") (pin "2") (pinfunction "2_2") (pintype "passive"))
    )
    (net (code "28") (name "Net-(DA2-PA4)") (class "Default")
      (node (ref "DA2") (pin "51") (pinfunction "PA4_51") (pintype "passive"))
      (node (ref "R25") (pin "1") (pinfunction "1_1") (pintype "passive"))
    )
    (net (code "29") (name "Net-(DA2-PA5)") (class "Default")
      (node (ref "DA2") (pin "50") (pinfunction "PA5_50") (pintype "passive"))
      (node (ref "R32") (pin "2") (pinfunction "2_2") (pintype "passive"))
      (node (ref "R40") (pin "1") (pinfunction "1_1") (pintype "passive"))
      (node (ref "VD2") (pin "2") (pinfunction "2_2") (pintype "passive"))
    )
    (net (code "30") (name "Net-(DA2-PA6)") (class "Default")
      (node (ref "DA2") (pin "49") (pinfunction "PA6_49") (pintype "passive"))
      (node (ref "R33") (pin "2") (pinfunction "2_2") (pintype "passive"))
    )
    (net (code "31") (name "Net-(DA2-PA7)") (class "Default")
      (node (ref "DA2") (pin "48") (pinfunction "PA7_48") (pintype "passive"))
      (node (ref "R34") (pin "2") (pinfunction "2_2") (pintype "passive"))
      (node (ref "R41") (pin "1") (pinfunction "1_1") (pintype "passive"))
      (node (ref "VD3") (pin "2") (pinfunction "2_2") (pintype "passive"))
    )
    (net (code "32") (name "Net-(DA2-PC1)") (class "Default")
      (node (ref "DA2") (pin "33") (pinfunction "PC1_33") (pintype "passive"))
      (node (ref "R35") (pin "2") (pinfunction "2_2") (pintype "passive"))
      (node (ref "R42") (pin "1") (pinfunction "1_1") (pintype "passive"))
      (node (ref "VD4") (pin "2") (pinfunction "2_2") (pintype "passive"))
    )
    (net (code "33") (name "Net-(DA2-PC2)") (class "Default")
      (node (ref "DA2") (pin "31") (pinfunction "PC2_31") (pintype "passive"))
      (node (ref "R36") (pin "2") (pinfunction "2_2") (pintype "passive"))
      (node (ref "R43") (pin "1") (pinfunction "1_1") (pintype "passive"))
      (node (ref "VD5") (pin "2") (pinfunction "2_2") (pintype "passive"))
    )
    (net (code "34") (name "Net-(DA2-PD0)") (class "Default")
      (node (ref "DA2") (pin "23") (pinfunction "PD0_23") (pintype "passive"))
      (node (ref "R58") (pin "2") (pinfunction "2_2") (pintype "passive"))
      (node (ref "X5") (pin "7") (pintype "passive"))
    )
    (net (code "35") (name "Net-(DA2-PD1)") (class "Default")
      (node (ref "DA2") (pin "24") (pinfunction "PD1_24") (pintype "passive"))
      (node (ref "R59") (pin "2") (pinfunction "2_2") (pintype "passive"))
      (node (ref "X5") (pin "9") (pintype "passive"))
    )
    (net (code "36") (name "Net-(DA2-PD2)") (class "Default")
      (node (ref "DA2") (pin "25") (pinfunction "PD2_25") (pintype "passive"))
      (node (ref "R60") (pin "2") (pinfunction "2_2") (pintype "passive"))
      (node (ref "X5") (pin "3") (pintype "passive"))
    )
    (net (code "37") (name "Net-(DA2-PD3)") (class "Default")
      (node (ref "DA2") (pin "26") (pinfunction "PD3_26") (pintype "passive"))
      (node (ref "R61") (pin "2") (pinfunction "2_2") (pintype "passive"))
      (node (ref "X5") (pin "5") (pintype "passive"))
    )
    (net (code "38") (name "Net-(DA2-PD4)") (class "Default")
      (node (ref "DA2") (pin "22") (pinfunction "PD4_22") (pintype "passive"))
      (node (ref "R62") (pin "2") (pinfunction "2_2") (pintype "passive"))
      (node (ref "X5") (pin "13") (pintype "passive"))
    )
    (net (code "39") (name "Net-(DA2-PD5)") (class "Default")
      (node (ref "DA2") (pin "27") (pinfunction "PD5_27") (pintype "passive"))
      (node (ref "R48") (pin "1") (pinfunction "1_1") (pintype "passive"))
    )
    (net (code "40") (name "Net-(DA2-PD6)") (class "Default")
      (node (ref "DA2") (pin "28") (pinfunction "PD6_28") (pintype "passive"))
      (node (ref "R49") (pin "1") (pinfunction "1_1") (pintype "passive"))
    )
    (net (code "41") (name "Net-(DA2-PD7)") (class "Default")
      (node (ref "DA2") (pin "21") (pinfunction "PD7_21") (pintype "passive"))
      (node (ref "R50") (pin "1") (pinfunction "1_1") (pintype "passive"))
    )
    (net (code "42") (name "Net-(DA2-PE2)") (class "Default")
      (node (ref "DA2") (pin "14") (pinfunction "PE2_14") (pintype "passive"))
      (node (ref "R23") (pin "2") (pinfunction "2_2") (pintype "passive"))
      (node (ref "VD1") (pin "2") (pinfunction "2_2") (pintype "passive"))
    )
    (net (code "43") (name "Net-(DA2-PF0)") (class "Default")
      (node (ref "DA2") (pin "58") (pinfunction "PF0_58") (pintype "passive"))
      (node (ref "DD1") (pin "20") (pinfunction "R1OUT_20") (pintype "passive"))
    )
    (net (code "44") (name "Net-(DA2-PF1)") (class "Default")
      (node (ref "DA2") (pin "59") (pinfunction "PF1_59") (pintype "passive"))
      (node (ref "DD1") (pin "14") (pinfunction "T1IN_14") (pintype "passive"))
      (node (ref "R64") (pin "1") (pinfunction "1_1") (pintype "passive"))
    )
    (net (code "45") (name "Net-(DA2-PF3)") (class "Default")
      (node (ref "DA2") (pin "61") (pinfunction "PF3_61") (pintype "passive"))
      (node (ref "R51") (pin "2") (pinfunction "2_2") (pintype "passive"))
    )
    (net (code "46") (name "Net-(DA2-PF4)") (class "Default")
      (node (ref "DA2") (pin "62") (pinfunction "PF4_62") (pintype "passive"))
      (node (ref "R54") (pin "1") (pinfunction "1_1") (pintype "passive"))
    )
    (net (code "47") (name "Net-(DA2-PF5)") (class "Default")
      (node (ref "C6") (pin "2") (pinfunction "2_2") (pintype "passive"))
      (node (ref "DA2") (pin "63") (pinfunction "PF5_63") (pintype "passive"))
      (node (ref "R52") (pin "2") (pinfunction "2_2") (pintype "passive"))
      (node (ref "SA1") (pin "2") (pinfunction "2_2") (pintype "passive"))
    )
    (net (code "48") (name "Net-(DA2-PF6)") (class "Default")
      (node (ref "C7") (pin "2") (pinfunction "2_2") (pintype "passive"))
      (node (ref "DA2") (pin "64") (pinfunction "PF6_64") (pintype "passive"))
      (node (ref "R53") (pin "2") (pinfunction "2_2") (pintype "passive"))
      (node (ref "SA1") (pin "4") (pinfunction "4_4") (pintype "passive"))
    )
    (net (code "49") (name "Net-(DA2-RESET)") (class "Default")
      (node (ref "C15") (pin "1") (pinfunction "1_1") (pintype "passive"))
      (node (ref "DA2") (pin "10") (pinfunction "RESET_10") (pintype "passive"))
      (node (ref "R57") (pin "2") (pinfunction "2_2") (pintype "passive"))
      (node (ref "X5") (pin "15") (pintype "passive"))
    )
    (net (code "50") (name "Net-(DD1-C1+)") (class "Default")
      (node (ref "C20") (pin "1") (pinfunction "1_1") (pintype "passive"))
      (node (ref "DD1") (pin "27") (pinfunction "C1+_27") (pintype "passive"))
    )
    (net (code "51") (name "Net-(DD1-C1-)") (class "Default")
      (node (ref "C20") (pin "2") (pinfunction "2_2") (pintype "passive"))
      (node (ref "DD1") (pin "25") (pinfunction "C1-_25") (pintype "passive"))
    )
    (net (code "52") (name "Net-(DD1-C2+)") (class "Default")
      (node (ref "C18") (pin "1") (pinfunction "1_1") (pintype "passive"))
      (node (ref "DD1") (pin "1") (pinfunction "C2+_1") (pintype "passive"))
    )
    (net (code "53") (name "Net-(DD1-C2-)") (class "Default")
      (node (ref "C18") (pin "2") (pinfunction "2_2") (pintype "passive"))
      (node (ref "DD1") (pin "3") (pinfunction "C2-_3") (pintype "passive"))
    )
    (net (code "54") (name "Net-(DD1-EN)") (class "Default")
      (node (ref "DD1") (pin "17") (pinfunction "EN_17") (pintype "passive"))
      (node (ref "R65") (pin "2") (pinfunction "2_2") (pintype "passive"))
    )
    (net (code "55") (name "Net-(DD1-R1IN)") (class "Default")
      (node (ref "DD1") (pin "18") (pinfunction "R1IN_18") (pintype "passive"))
      (node (ref "R67") (pin "1") (pinfunction "1_1") (pintype "passive"))
    )
    (net (code "56") (name "Net-(DD1-SHDN)") (class "Default")
      (node (ref "DD1") (pin "16") (pinfunction "SHDN_16") (pintype "passive"))
      (node (ref "R63") (pin "2") (pinfunction "2_2") (pintype "passive"))
    )
    (net (code "57") (name "Net-(DD1-T1OUT)") (class "Default")
      (node (ref "DD1") (pin "5") (pinfunction "T1OUT_5") (pintype "passive"))
      (node (ref "R66") (pin "1") (pinfunction "1_1") (pintype "passive"))
    )
    (net (code "58") (name "Net-(DD1-Uh)") (class "Default")
      (node (ref "C16") (pin "1") (pinfunction "1_1") (pintype "passive"))
      (node (ref "DD1") (pin "28") (pinfunction "Uh_28") (pintype "passive"))
    )
    (net (code "59") (name "Net-(DD1-Ul)") (class "Default")
      (node (ref "C17") (pin "2") (pinfunction "2_2") (pintype "passive"))
      (node (ref "DD1") (pin "4") (pinfunction "Ul_4") (pintype "passive"))
    )
    (net (code "60") (name "Net-(R1-Pad1)") (class "Default")
      (node (ref "R1") (pin "1") (pinfunction "1_1") (pintype "passive"))
      (node (ref "X1") (pin "1") (pinfunction "1_1") (pintype "passive"))
    )
    (net (code "61") (name "Net-(R2-Pad1)") (class "Default")
      (node (ref "R2") (pin "1") (pinfunction "1_1") (pintype "passive"))
      (node (ref "X1") (pin "2") (pinfunction "2_2") (pintype "passive"))
    )
    (net (code "62") (name "Net-(R3-Pad1)") (class "Default")
      (node (ref "R3") (pin "1") (pinfunction "1_1") (pintype "passive"))
      (node (ref "X1") (pin "3") (pinfunction "3_3") (pintype "passive"))
    )
    (net (code "63") (name "Net-(R4-Pad1)") (class "Default")
      (node (ref "R4") (pin "1") (pinfunction "1_1") (pintype "passive"))
      (node (ref "X1") (pin "4") (pinfunction "4_4") (pintype "passive"))
    )
    (net (code "64") (name "Net-(R5-Pad1)") (class "Default")
      (node (ref "R5") (pin "1") (pinfunction "1_1") (pintype "passive"))
      (node (ref "X1") (pin "5") (pinfunction "5_5") (pintype "passive"))
    )
    (net (code "65") (name "Net-(R6-Pad1)") (class "Default")
      (node (ref "R6") (pin "1") (pinfunction "1_1") (pintype "passive"))
      (node (ref "X1") (pin "6") (pinfunction "6_6") (pintype "passive"))
    )
    (net (code "66") (name "Net-(R7-Pad1)") (class "Default")
      (node (ref "R7") (pin "1") (pinfunction "1_1") (pintype "passive"))
      (node (ref "X1") (pin "7") (pinfunction "7_7") (pintype "passive"))
    )
    (net (code "67") (name "Net-(R8-Pad1)") (class "Default")
      (node (ref "R8") (pin "1") (pinfunction "1_1") (pintype "passive"))
      (node (ref "X1") (pin "8") (pinfunction "8_8") (pintype "passive"))
    )
    (net (code "68") (name "Net-(R9-Pad1)") (class "Default")
      (node (ref "R9") (pin "1") (pinfunction "1_1") (pintype "passive"))
      (node (ref "X1") (pin "9") (pinfunction "9_9") (pintype "passive"))
    )
    (net (code "69") (name "Net-(R10-Pad1)") (class "Default")
      (node (ref "R10") (pin "1") (pinfunction "1_1") (pintype "passive"))
      (node (ref "X1") (pin "10") (pinfunction "10_10") (pintype "passive"))
    )
    (net (code "70") (name "Net-(R11-Pad1)") (class "Default")
      (node (ref "R11") (pin "1") (pinfunction "1_1") (pintype "passive"))
      (node (ref "X1") (pin "14") (pinfunction "14_14") (pintype "passive"))
    )
    (net (code "71") (name "Net-(R12-Pad1)") (class "Default")
      (node (ref "R12") (pin "1") (pinfunction "1_1") (pintype "passive"))
      (node (ref "X1") (pin "15") (pinfunction "15_15") (pintype "passive"))
    )
    (net (code "72") (name "Net-(R13-Pad1)") (class "Default")
      (node (ref "R13") (pin "1") (pinfunction "1_1") (pintype "passive"))
      (node (ref "X1") (pin "16") (pinfunction "16_16") (pintype "passive"))
    )
    (net (code "73") (name "Net-(R14-Pad1)") (class "Default")
      (node (ref "R14") (pin "1") (pinfunction "1_1") (pintype "passive"))
      (node (ref "X1") (pin "17") (pinfunction "17_17") (pintype "passive"))
    )
    (net (code "74") (name "Net-(R15-Pad1)") (class "Default")
      (node (ref "R15") (pin "1") (pinfunction "1_1") (pintype "passive"))
      (node (ref "X1") (pin "18") (pinfunction "18_18") (pintype "passive"))
    )
    (net (code "75") (name "Net-(R16-Pad1)") (class "Default")
      (node (ref "R16") (pin "1") (pinfunction "1_1") (pintype "passive"))
      (node (ref "X1") (pin "19") (pinfunction "19_19") (pintype "passive"))
    )
    (net (code "76") (name "Net-(R17-Pad1)") (class "Default")
      (node (ref "R17") (pin "1") (pinfunction "1_1") (pintype "passive"))
      (node (ref "X1") (pin "20") (pinfunction "20_20") (pintype "passive"))
    )
    (net (code "77") (name "Net-(R18-Pad1)") (class "Default")
      (node (ref "R18") (pin "1") (pinfunction "1_1") (pintype "passive"))
      (node (ref "X1") (pin "21") (pinfunction "21_21") (pintype "passive"))
    )
    (net (code "78") (name "Net-(R19-Pad1)") (class "Default")
      (node (ref "R19") (pin "1") (pinfunction "1_1") (pintype "passive"))
      (node (ref "X1") (pin "22") (pinfunction "22_22") (pintype "passive"))
    )
    (net (code "79") (name "Net-(R21-Pad1)") (class "Default")
      (node (ref "R21") (pin "1") (pinfunction "1_1") (pintype "passive"))
      (node (ref "X3") (pin "1") (pintype "passive"))
    )
    (net (code "80") (name "Net-(R21-Pad2)") (class "Default")
      (node (ref "R21") (pin "2") (pinfunction "2_2") (pintype "passive"))
      (node (ref "R24") (pin "2") (pinfunction "2_2") (pintype "passive"))
      (node (ref "VT1") (pin "3") (pinfunction "3_3") (pintype "passive"))
    )
    (net (code "81") (name "Net-(R22-Pad2)") (class "Default")
      (node (ref "R22") (pin "2") (pinfunction "2_2") (pintype "passive"))
      (node (ref "R23") (pin "1") (pinfunction "1_1") (pintype "passive"))
      (node (ref "X4") (pin "1") (pintype "passive"))
    )
    (net (code "82") (name "Net-(R25-Pad2)") (class "Default")
      (node (ref "R25") (pin "2") (pinfunction "2_2") (pintype "passive"))
      (node (ref "VT1") (pin "2") (pinfunction "2_2") (pintype "passive"))
    )
    (net (code "83") (name "Net-(R48-Pad2)") (class "Default")
      (node (ref "R48") (pin "2") (pinfunction "2_2") (pintype "passive"))
      (node (ref "VD8") (pin "1") (pinfunction "1_1") (pintype "passive"))
    )
    (net (code "84") (name "Net-(R49-Pad2)") (class "Default")
      (node (ref "R49") (pin "2") (pinfunction "2_2") (pintype "passive"))
      (node (ref "VD7") (pin "1") (pinfunction "1_1") (pintype "passive"))
    )
    (net (code "85") (name "Net-(R50-Pad2)") (class "Default")
      (node (ref "R50") (pin "2") (pinfunction "2_2") (pintype "passive"))
      (node (ref "VD6") (pin "1") (pinfunction "1_1") (pintype "passive"))
    )
    (net (code "86") (name "Net-(R55-Pad1)") (class "Default")
      (node (ref "R55") (pin "1") (pinfunction "1_1") (pintype "passive"))
      (node (ref "SA1") (pin "1") (pinfunction "1_1") (pintype "passive"))
    )
    (net (code "87") (name "Net-(R56-Pad1)") (class "Default")
      (node (ref "R56") (pin "1") (pinfunction "1_1") (pintype "passive"))
      (node (ref "SA1") (pin "3") (pinfunction "3_3") (pintype "passive"))
    )
    (net (code "88") (name "Net-(R66-Pad2)") (class "Default")
      (node (ref "R66") (pin "2") (pinfunction "2_2") (pintype "passive"))
      (node (ref "X6") (pin "3") (pintype "passive"))
    )
    (net (code "89") (name "Net-(R67-Pad2)") (class "Default")
      (node (ref "R67") (pin "2") (pinfunction "2_2") (pintype "passive"))
      (node (ref "X6") (pin "2") (pintype "passive"))
    )
    (net (code "90") (name "unconnected-(DA2-DN-Pad2)") (class "Default")
      (node (ref "DA2") (pin "2") (pinfunction "DN_2") (pintype "passive"))
    )
    (net (code "91") (name "unconnected-(DA2-DP-Pad1)") (class "Default")
      (node (ref "DA2") (pin "1") (pinfunction "DP_1") (pintype "passive"))
    )
    (net (code "92") (name "unconnected-(DA2-NC-Pad32)") (class "Default")
      (node (ref "DA2") (pin "32") (pinfunction "NC_32") (pintype "passive"))
    )
    (net (code "93") (name "unconnected-(DA2-PA0-Pad55)") (class "Default")
      (node (ref "DA2") (pin "55") (pinfunction "PA0_55") (pintype "passive"))
    )
    (net (code "94") (name "unconnected-(DA2-PE0-Pad18)") (class "Default")
      (node (ref "DA2") (pin "18") (pinfunction "PE0_18") (pintype "passive"))
    )
    (net (code "95") (name "unconnected-(DA2-PE1-Pad17)") (class "Default")
      (node (ref "DA2") (pin "17") (pinfunction "PE1_17") (pintype "passive"))
    )
    (net (code "96") (name "unconnected-(DA2-PE3-Pad13)") (class "Default")
      (node (ref "DA2") (pin "13") (pinfunction "PE3_13") (pintype "passive"))
    )
    (net (code "97") (name "unconnected-(DA2-PE6-Pad8)") (class "Default")
      (node (ref "DA2") (pin "8") (pinfunction "PE6_8") (pintype "passive"))
    )
    (net (code "98") (name "unconnected-(DA2-PE7-Pad7)") (class "Default")
      (node (ref "DA2") (pin "7") (pinfunction "PE7_7") (pintype "passive"))
    )
    (net (code "99") (name "unconnected-(DA2-PF2-Pad60)") (class "Default")
      (node (ref "DA2") (pin "60") (pinfunction "PF2_60") (pintype "passive"))
    )
    (net (code "100") (name "unconnected-(DA2-STANDBY-Pad6)") (class "Default")
      (node (ref "DA2") (pin "6") (pinfunction "STANDBY_6") (pintype "passive"))
    )
    (net (code "101") (name "unconnected-(DA2-WAKEUP-Pad9)") (class "Default")
      (node (ref "DA2") (pin "9") (pinfunction "WAKEUP_9") (pintype "passive"))
    )
    (net (code "102") (name "unconnected-(DD1-R1OUTB-Pad19)") (class "Default")
      (node (ref "DD1") (pin "19") (pinfunction "R1OUTB_19") (pintype "passive"))
    )
    (net (code "103") (name "unconnected-(DD1-R2IN-Pad24)") (class "Default")
      (node (ref "DD1") (pin "24") (pinfunction "R2IN_24") (pintype "passive"))
    )
    (net (code "104") (name "unconnected-(DD1-R2OUT-Pad21)") (class "Default")
      (node (ref "DD1") (pin "21") (pinfunction "R2OUT_21") (pintype "passive"))
    )
    (net (code "105") (name "unconnected-(DD1-R3IN-Pad23)") (class "Default")
      (node (ref "DD1") (pin "23") (pinfunction "R3IN_23") (pintype "passive"))
    )
    (net (code "106") (name "unconnected-(DD1-R3OUT-Pad22)") (class "Default")
      (node (ref "DD1") (pin "22") (pinfunction "R3OUT_22") (pintype "passive"))
    )
    (net (code "107") (name "unconnected-(DD1-T2IN-Pad13)") (class "Default")
      (node (ref "DD1") (pin "13") (pinfunction "T2IN_13") (pintype "passive"))
    )
    (net (code "108") (name "unconnected-(DD1-T2OUT-Pad6)") (class "Default")
      (node (ref "DD1") (pin "6") (pinfunction "T2OUT_6") (pintype "passive"))
    )
    (net (code "109") (name "unconnected-(DD1-T3IN-Pad12)") (class "Default")
      (node (ref "DD1") (pin "12") (pinfunction "T3IN_12") (pintype "passive"))
    )
    (net (code "110") (name "unconnected-(DD1-T3OUT-Pad7)") (class "Default")
      (node (ref "DD1") (pin "7") (pinfunction "T3OUT_7") (pintype "passive"))
    )
    (net (code "111") (name "unconnected-(DD1-T4IN-Pad11)") (class "Default")
      (node (ref "DD1") (pin "11") (pinfunction "T4IN_11") (pintype "passive"))
    )
    (net (code "112") (name "unconnected-(DD1-T4OUT-Pad8)") (class "Default")
      (node (ref "DD1") (pin "8") (pinfunction "T4OUT_8") (pintype "passive"))
    )
    (net (code "113") (name "unconnected-(DD1-T5IN-Pad10)") (class "Default")
      (node (ref "DD1") (pin "10") (pinfunction "T5IN_10") (pintype "passive"))
    )
    (net (code "114") (name "unconnected-(DD1-T5OUT-Pad9)") (class "Default")
      (node (ref "DD1") (pin "9") (pinfunction "T5OUT_9") (pintype "passive"))
    )
    (net (code "115") (name "unconnected-(X1-Pad11)") (class "Default")
      (node (ref "X1") (pin "11") (pinfunction "11_11") (pintype "passive"))
    )
    (net (code "116") (name "unconnected-(X1-Pad12)") (class "Default")
      (node (ref "X1") (pin "12") (pinfunction "12_12") (pintype "passive"))
    )
    (net (code "117") (name "unconnected-(X1-Pad13)") (class "Default")
      (node (ref "X1") (pin "13") (pinfunction "13_13") (pintype "passive"))
    )
    (net (code "118") (name "unconnected-(X1-Pad25)") (class "Default")
      (node (ref "X1") (pin "25") (pinfunction "25_25") (pintype "passive"))
    )
    (net (code "119") (name "unconnected-(X2-Pad1A)") (class "Default")
      (node (ref "X2") (pin "1A") (pinfunction "1A_1A") (pintype "passive"))
    )
    (net (code "120") (name "unconnected-(X2-Pad9A)") (class "Default")
      (node (ref "X2") (pin "9A") (pinfunction "9A_9A") (pintype "passive"))
    )
    (net (code "121") (name "unconnected-(X2-Pad9B)") (class "Default")
      (node (ref "X2") (pin "9B") (pinfunction "9B_9B") (pintype "passive"))
    )
    (net (code "122") (name "unconnected-(X2-Pad10A)") (class "Default")
      (node (ref "X2") (pin "10A") (pinfunction "10A_10A") (pintype "passive"))
    )
    (net (code "123") (name "unconnected-(X2-Pad10B)") (class "Default")
      (node (ref "X2") (pin "10B") (pinfunction "10B_10B") (pintype "passive"))
    )
    (net (code "124") (name "unconnected-(X2-Pad11A)") (class "Default")
      (node (ref "X2") (pin "11A") (pinfunction "11A_11A") (pintype "passive"))
    )
    (net (code "125") (name "unconnected-(X2-Pad11B)") (class "Default")
      (node (ref "X2") (pin "11B") (pinfunction "11B_11B") (pintype "passive"))
    )
    (net (code "126") (name "unconnected-(X2-Pad12A)") (class "Default")
      (node (ref "X2") (pin "12A") (pinfunction "12A_12A") (pintype "passive"))
    )
    (net (code "127") (name "unconnected-(X2-Pad12B)") (class "Default")
      (node (ref "X2") (pin "12B") (pinfunction "12B_12B") (pintype "passive"))
    )
    (net (code "128") (name "unconnected-(X2-Pad13B)") (class "Default")
      (node (ref "X2") (pin "13B") (pinfunction "13B_13B") (pintype "passive"))
    )
    (net (code "129") (name "unconnected-(X2-Pad14A)") (class "Default")
      (node (ref "X2") (pin "14A") (pinfunction "14A_14A") (pintype "passive"))
    )
    (net (code "130") (name "unconnected-(X2-Pad15A)") (class "Default")
      (node (ref "X2") (pin "15A") (pinfunction "15A_15A") (pintype "passive"))
    )
    (net (code "131") (name "unconnected-(X2-Pad15B)") (class "Default")
      (node (ref "X2") (pin "15B") (pinfunction "15B_15B") (pintype "passive"))
    )
    (net (code "132") (name "unconnected-(X2-Pad16A)") (class "Default")
      (node (ref "X2") (pin "16A") (pinfunction "16A_16A") (pintype "passive"))
    )
    (net (code "133") (name "unconnected-(X2-Pad16B)") (class "Default")
      (node (ref "X2") (pin "16B") (pinfunction "16B_16B") (pintype "passive"))
    )
    (net (code "134") (name "unconnected-(X2-Pad17A)") (class "Default")
      (node (ref "X2") (pin "17A") (pinfunction "17A_17A") (pintype "passive"))
    )
    (net (code "135") (name "unconnected-(X2-Pad17B)") (class "Default")
      (node (ref "X2") (pin "17B") (pinfunction "17B_17B") (pintype "passive"))
    )
    (net (code "136") (name "unconnected-(X2-Pad18A)") (class "Default")
      (node (ref "X2") (pin "18A") (pinfunction "18A_18A") (pintype "passive"))
    )
    (net (code "137") (name "unconnected-(X2-Pad18B)") (class "Default")
      (node (ref "X2") (pin "18B") (pinfunction "18B_18B") (pintype "passive"))
    )
    (net (code "138") (name "unconnected-(X2-Pad19A)") (class "Default")
      (node (ref "X2") (pin "19A") (pinfunction "19A_19A") (pintype "passive"))
    )
    (net (code "139") (name "unconnected-(X2-Pad19B)") (class "Default")
      (node (ref "X2") (pin "19B") (pinfunction "19B_19B") (pintype "passive"))
    )
    (net (code "140") (name "unconnected-(X2-Pad20B)") (class "Default")
      (node (ref "X2") (pin "20B") (pinfunction "20B_20B") (pintype "passive"))
    )
    (net (code "141") (name "unconnected-(X2-Pad21A)") (class "Default")
      (node (ref "X2") (pin "21A") (pinfunction "21A_21A") (pintype "passive"))
    )
    (net (code "142") (name "unconnected-(X2-Pad21B)") (class "Default")
      (node (ref "X2") (pin "21B") (pinfunction "21B_21B") (pintype "passive"))
    )
    (net (code "143") (name "unconnected-(X2-Pad22A)") (class "Default")
      (node (ref "X2") (pin "22A") (pinfunction "22A_22A") (pintype "passive"))
    )
    (net (code "144") (name "unconnected-(X2-Pad22B)") (class "Default")
      (node (ref "X2") (pin "22B") (pinfunction "22B_22B") (pintype "passive"))
    )
    (net (code "145") (name "unconnected-(X2-Pad23A)") (class "Default")
      (node (ref "X2") (pin "23A") (pinfunction "23A_23A") (pintype "passive"))
    )
    (net (code "146") (name "unconnected-(X2-Pad23B)") (class "Default")
      (node (ref "X2") (pin "23B") (pinfunction "23B_23B") (pintype "passive"))
    )
    (net (code "147") (name "unconnected-(X2-Pad25A)") (class "Default")
      (node (ref "X2") (pin "25A") (pinfunction "25A_25A") (pintype "passive"))
    )
    (net (code "148") (name "unconnected-(X2-Pad25B)") (class "Default")
      (node (ref "X2") (pin "25B") (pinfunction "25B_25B") (pintype "passive"))
    )
    (net (code "149") (name "unconnected-(X2-Pad26A)") (class "Default")
      (node (ref "X2") (pin "26A") (pinfunction "26A_26A") (pintype "passive"))
    )
    (net (code "150") (name "unconnected-(X2-Pad26B)") (class "Default")
      (node (ref "X2") (pin "26B") (pinfunction "26B_26B") (pintype "passive"))
    )
    (net (code "151") (name "unconnected-(X2-Pad27A)") (class "Default")
      (node (ref "X2") (pin "27A") (pinfunction "27A_27A") (pintype "passive"))
    )
    (net (code "152") (name "unconnected-(X2-Pad29A)") (class "Default")
      (node (ref "X2") (pin "29A") (pinfunction "29A_29A") (pintype "passive"))
    )
    (net (code "153") (name "unconnected-(X2-Pad31A)") (class "Default")
      (node (ref "X2") (pin "31A") (pinfunction "31A_31A") (pintype "passive"))
    )
    (net (code "154") (name "unconnected-(X5-Pad11)") (class "Default")
      (node (ref "X5") (pin "11") (pintype "passive"))
    )
    (net (code "155") (name "unconnected-(X5-Pad17)") (class "Default")
      (node (ref "X5") (pin "17") (pintype "passive"))
    )
    (net (code "156") (name "unconnected-(X5-Pad19)") (class "Default")
      (node (ref "X5") (pin "19") (pintype "passive"))
    )
    (net (code "157") (name "unconnected-(X6-Pad1)") (class "Default")
      (node (ref "X6") (pin "1") (pintype "passive"))
    )
    (net (code "158") (name "unconnected-(X6-Pad4)") (class "Default")
      (node (ref "X6") (pin "4") (pintype "passive"))
    )
    (net (code "159") (name "unconnected-(X6-Pad6)") (class "Default")
      (node (ref "X6") (pin "6") (pintype "passive"))
    )
    (net (code "160") (name "unconnected-(X6-Pad7)") (class "Default")
      (node (ref "X6") (pin "7") (pintype "passive"))
    )
    (net (code "161") (name "unconnected-(X6-Pad8)") (class "Default")
      (node (ref "X6") (pin "8") (pintype "passive"))
    )
    (net (code "162") (name "unconnected-(X6-Pad9)") (class "Default")
      (node (ref "X6") (pin "9") (pintype "passive"))
    )
  )
)
